# Arduino.net
KiCad netlist of a schematic drawn in Altium Designer
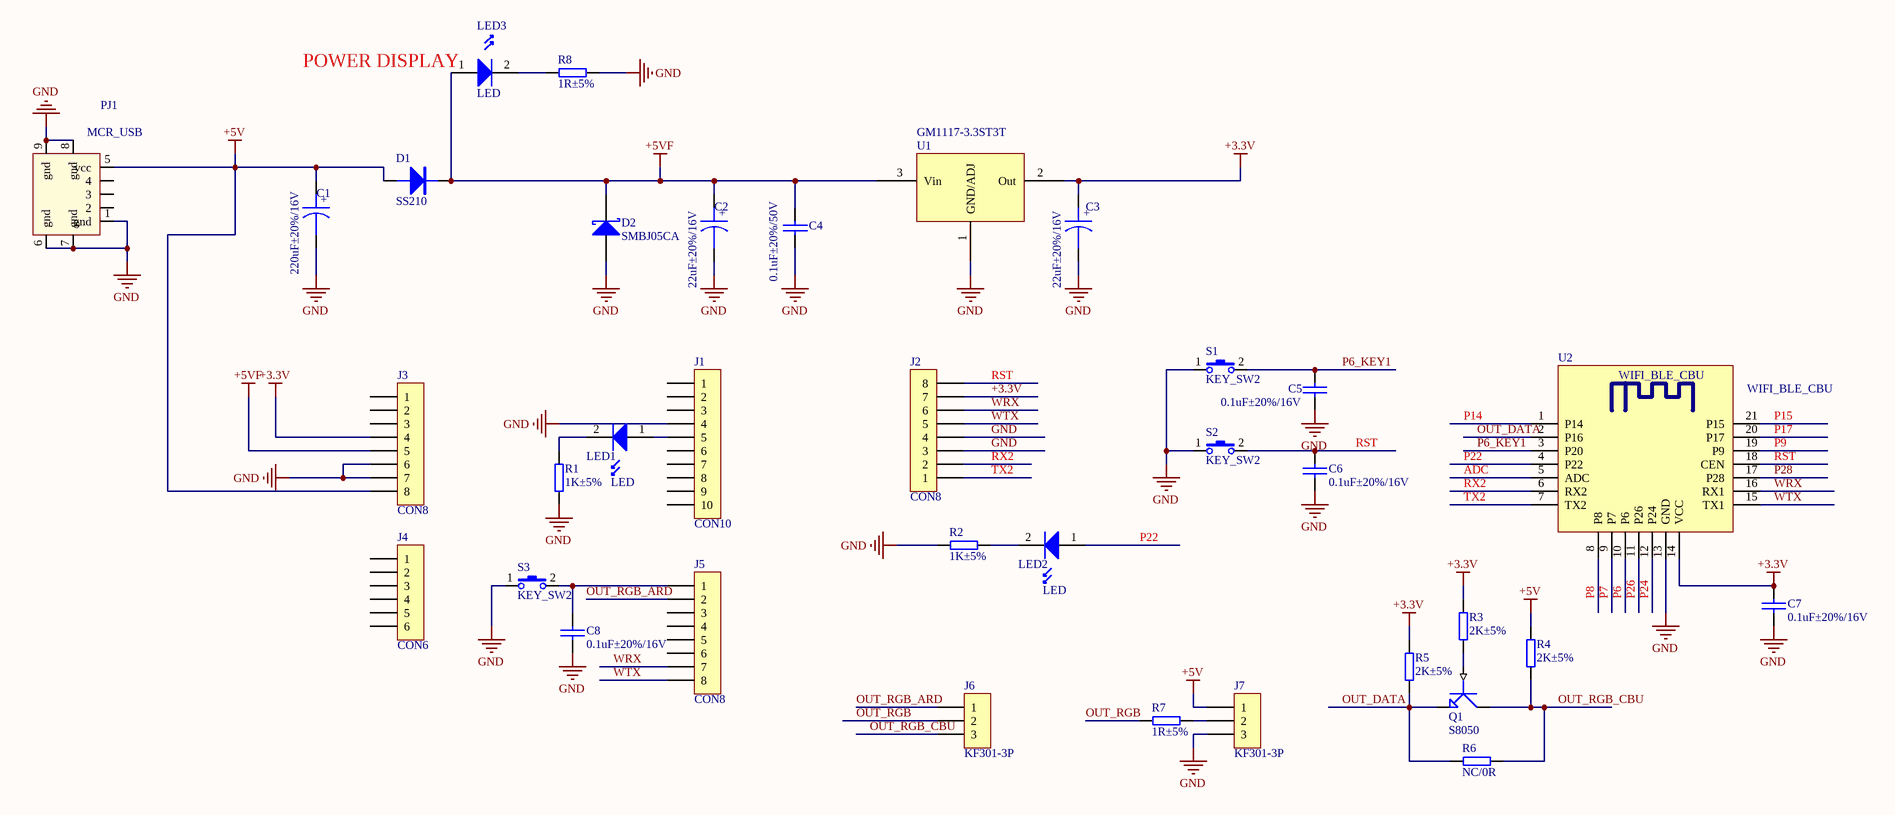
[diagram p0: Arduino幻彩灯带.SchDoc]

(export (version "E")
  (design (tool "Eeschema 10.0.6"))
  (components
    (comp (ref "C1")
      (value "220uF±20%/16V")
      (footprint "CD0.15")
      (description "Capacitor")
      (libsource (lib "*") (part "CAPACITOR POL"))
    )
    (comp (ref "C2")
      (value "22uF±20%/16V")
      (footprint "钽电容B3528")
      (description "Capacitor")
      (libsource (lib "*") (part "CAPACITOR POL"))
    )
    (comp (ref "C3")
      (value "22uF±20%/16V")
      (footprint "钽电容B3528")
      (description "Capacitor")
      (libsource (lib "*") (part "CAPACITOR POL"))
    )
    (comp (ref "C4")
      (value "0.1uF±20%/50V")
      (footprint "C0603")
      (description "Capacitor")
      (libsource (lib "昊华元件库sch") (part "CAP"))
    )
    (comp (ref "C5")
      (value "0.1uF±20%/16V")
      (footprint "C0603")
      (description "Capacitor")
      (libsource (lib "昊华元件库sch") (part "CAP"))
    )
    (comp (ref "C6")
      (value "0.1uF±20%/16V")
      (footprint "C0603")
      (description "Capacitor")
      (libsource (lib "昊华元件库sch") (part "CAP"))
    )
    (comp (ref "C7")
      (value "0.1uF±20%/16V")
      (footprint "C0603")
      (description "Capacitor")
      (libsource (lib "昊华元件库sch") (part "CAP"))
    )
    (comp (ref "C8")
      (value "0.1uF±20%/16V")
      (footprint "C0603")
      (description "Capacitor")
      (libsource (lib "昊华元件库sch") (part "CAP"))
    )
    (comp (ref "D1")
      (value "SS210")
      (footprint "SMA(DO-214AC)")
      (description "Diode")
      (libsource (lib "小马元件库sch") (part "Diode1"))
    )
    (comp (ref "D2")
      (value "SMBJ05CA")
      (footprint "SMB(DO-214AA)")
      (description "Schottky Diode")
      (fields (field (name "MFR") "Toshiba"))
      (libsource (lib "Miscellaneous Devices") (part "D Schottky"))
    )
    (comp (ref "J1")
      (value "CON10")
      (footprint "HDR1X10Z")
      (description "Connector")
      (libsource (lib "小马元件库sch") (part "CON10"))
    )
    (comp (ref "J2")
      (value "CON8")
      (footprint "HDR1X8Z")
      (description "Connector")
      (libsource (lib "小马元件库sch") (part "CON8"))
    )
    (comp (ref "J3")
      (value "CON8")
      (footprint "HDR1X8Z")
      (description "Connector")
      (libsource (lib "") (part "CON8_1"))
    )
    (comp (ref "J4")
      (value "CON6")
      (footprint "HDR1X6Z")
      (description "Connector")
      (libsource (lib "小马元件库sch") (part "CON6"))
    )
    (comp (ref "J5")
      (value "CON8")
      (footprint "HDR1X8Z")
      (description "Connector")
      (libsource (lib "") (part "CON8_1"))
    )
    (comp (ref "J6")
      (value "KF301-3P")
      (footprint "SIP3 - 2.54")
      (description "Connector")
      (libsource (lib "小马元件库sch") (part "CON3"))
    )
    (comp (ref "J7")
      (value "KF301-3P")
      (footprint "SIP3 - 2.54")
      (description "Connector")
      (libsource (lib "小马元件库sch") (part "CON3"))
    )
    (comp (ref "LED1")
      (value "LED")
      (footprint "LED0805_1")
      (fields (field (name "PUBLISHER") "*"))
      (libsource (lib "小马元件库sch") (part "LED"))
    )
    (comp (ref "LED2")
      (value "LED")
      (footprint "LED0805_1")
      (fields (field (name "PUBLISHER") "*"))
      (libsource (lib "小马元件库sch") (part "LED"))
    )
    (comp (ref "LED3")
      (value "LED")
      (footprint "LED0805_1")
      (fields (field (name "PUBLISHER") "*"))
      (libsource (lib "小马元件库sch") (part "LED"))
    )
    (comp (ref "PJ1")
      (value "MCR_USB")
      (footprint "MICRO_USB-NEW-16.12.12")
      (fields (field (name "PUBLISHER") "*"))
      (libsource (lib "昊华元件库sch") (part "MCR_USB"))
    )
    (comp (ref "Q1")
      (value "S8050")
      (footprint "SOT-23-NPN")
      (description "NPN Transistor")
      (libsource (lib "小马元件库sch") (part "NPN"))
    )
    (comp (ref "R1") (value "1K±5%") (footprint "R0603") (libsource (lib "昊华元件库sch") (part "RES5")))
    (comp (ref "R2") (value "1K±5%") (footprint "R0603") (libsource (lib "昊华元件库sch") (part "RES5")))
    (comp (ref "R3") (value "2K±5%") (footprint "R0603") (libsource (lib "昊华元件库sch") (part "RES5")))
    (comp (ref "R4") (value "2K±5%") (footprint "R0603") (libsource (lib "昊华元件库sch") (part "RES5")))
    (comp (ref "R5") (value "2K±5%") (footprint "R0603") (libsource (lib "昊华元件库sch") (part "RES5")))
    (comp (ref "R6") (value "NC/0R") (footprint "R0603") (libsource (lib "昊华元件库sch") (part "RES5")))
    (comp (ref "R7") (value "1R±5%") (footprint "R0603") (libsource (lib "昊华元件库sch") (part "RES5")))
    (comp (ref "R8") (value "1R±5%") (footprint "R0603") (libsource (lib "昊华元件库sch") (part "RES5")))
    (comp (ref "S1") (value "KEY_SW2") (footprint "KEY4-SMD") (libsource (lib "小马元件库sch") (part "KEY_SW2")))
    (comp (ref "S2") (value "KEY_SW2") (footprint "KEY4-SMD") (libsource (lib "小马元件库sch") (part "KEY_SW2")))
    (comp (ref "S3") (value "KEY_SW2") (footprint "KEY4-SMD") (libsource (lib "小马元件库sch") (part "KEY_SW2")))
    (comp (ref "U1") (value "GM1117-3.3ST3T") (footprint "SOT-223") (libsource (lib "mylib") (part "GM1117")))
    (comp (ref "U2")
      (value "WIFI_BLE_CBU")
      (footprint "WIFI_BLE_CBU")
      (description "Module")
      (libsource (lib "TYModeSchlib V03") (part "WIFI_BLE_CBU"))
    )
  )
  (nets
    (net (code "1") (name "+3.3V") (class "Default")
      (node (ref "C3") (pin "1") (pinfunction "1_1") (pintype "passive"))
      (node (ref "C7") (pin "2") (pinfunction "2_2") (pintype "passive"))
      (node (ref "J2") (pin "7") (pinfunction "7_7") (pintype "passive"))
      (node (ref "J3") (pin "4") (pinfunction "4_4") (pintype "passive"))
      (node (ref "R3") (pin "1") (pinfunction "1_1") (pintype "passive"))
      (node (ref "R5") (pin "1") (pinfunction "1_1") (pintype "passive"))
      (node (ref "U1") (pin "2") (pinfunction "Out_2") (pintype "passive"))
      (node (ref "U2") (pin "14") (pinfunction "VCC_14") (pintype "passive"))
    )
    (net (code "2") (name "+5V") (class "Default")
      (node (ref "C1") (pin "1") (pinfunction "1_1") (pintype "passive"))
      (node (ref "D1") (pin "1") (pinfunction "1_1") (pintype "passive"))
      (node (ref "J3") (pin "8") (pinfunction "8_8") (pintype "passive"))
      (node (ref "J7") (pin "1") (pinfunction "1_1") (pintype "passive"))
      (node (ref "PJ1") (pin "5") (pinfunction "vcc_5") (pintype "passive"))
      (node (ref "R4") (pin "1") (pinfunction "1_1") (pintype "passive"))
    )
    (net (code "3") (name "+5VF") (class "Default")
      (node (ref "C2") (pin "1") (pinfunction "1_1") (pintype "passive"))
      (node (ref "C4") (pin "1") (pinfunction "1_1") (pintype "passive"))
      (node (ref "D1") (pin "2") (pinfunction "2_2") (pintype "passive"))
      (node (ref "D2") (pin "2") (pinfunction "K_2") (pintype "passive"))
      (node (ref "J3") (pin "5") (pinfunction "5_5") (pintype "passive"))
      (node (ref "LED3") (pin "1") (pinfunction "1_1") (pintype "passive"))
      (node (ref "U1") (pin "3") (pinfunction "Vin_3") (pintype "passive"))
    )
    (net (code "4") (name "/ADC") (class "Default")
      (node (ref "U2") (pin "5") (pinfunction "ADC_5") (pintype "passive"))
    )
    (net (code "5") (name "/OUT_DATA") (class "Default")
      (node (ref "Q1") (pin "1") (pinfunction "E_1") (pintype "passive"))
      (node (ref "R5") (pin "2") (pinfunction "2_2") (pintype "passive"))
      (node (ref "R6") (pin "1") (pinfunction "1_1") (pintype "passive"))
      (node (ref "U2") (pin "2") (pinfunction "P16_2") (pintype "passive"))
    )
    (net (code "6") (name "/OUT_RGB") (class "Default")
      (node (ref "J6") (pin "2") (pinfunction "2_2") (pintype "passive"))
      (node (ref "R7") (pin "1") (pinfunction "1_1") (pintype "passive"))
    )
    (net (code "7") (name "/OUT_RGB_ARD") (class "Default")
      (node (ref "J5") (pin "2") (pinfunction "2_2") (pintype "passive"))
      (node (ref "J6") (pin "1") (pinfunction "1_1") (pintype "passive"))
    )
    (net (code "8") (name "/OUT_RGB_CBU") (class "Default")
      (node (ref "J6") (pin "3") (pinfunction "3_3") (pintype "passive"))
      (node (ref "Q1") (pin "3") (pinfunction "C_3") (pintype "passive"))
      (node (ref "R4") (pin "2") (pinfunction "2_2") (pintype "passive"))
      (node (ref "R6") (pin "2") (pinfunction "2_2") (pintype "passive"))
    )
    (net (code "9") (name "/P6") (class "Default")
      (node (ref "U2") (pin "10") (pinfunction "P6_10") (pintype "passive"))
    )
    (net (code "10") (name "/P6_KEY1") (class "Default")
      (node (ref "C5") (pin "2") (pinfunction "2_2") (pintype "passive"))
      (node (ref "S1") (pin "2") (pinfunction "2_2") (pintype "passive"))
      (node (ref "U2") (pin "3") (pinfunction "P20_3") (pintype "passive"))
    )
    (net (code "11") (name "/P7") (class "Default")
      (node (ref "U2") (pin "9") (pinfunction "P7_9") (pintype "passive"))
    )
    (net (code "12") (name "/P8") (class "Default")
      (node (ref "U2") (pin "8") (pinfunction "P8_8") (pintype "passive"))
    )
    (net (code "13") (name "/P9") (class "Default")
      (node (ref "U2") (pin "19") (pinfunction "P9_19") (pintype "passive"))
    )
    (net (code "14") (name "/P14") (class "Default")
      (node (ref "U2") (pin "1") (pinfunction "P14_1") (pintype "passive"))
    )
    (net (code "15") (name "/P15") (class "Default")
      (node (ref "U2") (pin "21") (pinfunction "P15_21") (pintype "passive"))
    )
    (net (code "16") (name "/P17") (class "Default")
      (node (ref "U2") (pin "20") (pinfunction "P17_20") (pintype "passive"))
    )
    (net (code "17") (name "/P22") (class "Default")
      (node (ref "LED2") (pin "1") (pinfunction "1_1") (pintype "passive"))
      (node (ref "U2") (pin "4") (pinfunction "P22_4") (pintype "passive"))
    )
    (net (code "18") (name "/P24") (class "Default")
      (node (ref "U2") (pin "12") (pinfunction "P24_12") (pintype "passive"))
    )
    (net (code "19") (name "/P26") (class "Default")
      (node (ref "U2") (pin "11") (pinfunction "P26_11") (pintype "passive"))
    )
    (net (code "20") (name "/P28") (class "Default")
      (node (ref "U2") (pin "17") (pinfunction "P28_17") (pintype "passive"))
    )
    (net (code "21") (name "/RST") (class "Default")
      (node (ref "C6") (pin "1") (pinfunction "1_1") (pintype "passive"))
      (node (ref "J2") (pin "8") (pinfunction "8_8") (pintype "passive"))
      (node (ref "S2") (pin "2") (pinfunction "2_2") (pintype "passive"))
      (node (ref "U2") (pin "18") (pinfunction "CEN_18") (pintype "passive"))
    )
    (net (code "22") (name "/RX2") (class "Default")
      (node (ref "J2") (pin "2") (pinfunction "2_2") (pintype "passive"))
      (node (ref "U2") (pin "6") (pinfunction "RX2_6") (pintype "passive"))
    )
    (net (code "23") (name "/TX2") (class "Default")
      (node (ref "J2") (pin "1") (pinfunction "1_1") (pintype "passive"))
      (node (ref "U2") (pin "7") (pinfunction "TX2_7") (pintype "passive"))
    )
    (net (code "24") (name "/WRX") (class "Default")
      (node (ref "J2") (pin "6") (pinfunction "6_6") (pintype "passive"))
      (node (ref "J5") (pin "7") (pinfunction "7_7") (pintype "passive"))
      (node (ref "U2") (pin "16") (pinfunction "RX1_16") (pintype "passive"))
    )
    (net (code "25") (name "/WTX") (class "Default")
      (node (ref "J2") (pin "5") (pinfunction "5_5") (pintype "passive"))
      (node (ref "J5") (pin "8") (pinfunction "8_8") (pintype "passive"))
      (node (ref "U2") (pin "15") (pinfunction "TX1_15") (pintype "passive"))
    )
    (net (code "26") (name "GND") (class "Default")
      (node (ref "C1") (pin "2") (pinfunction "2_2") (pintype "passive"))
      (node (ref "C2") (pin "2") (pinfunction "2_2") (pintype "passive"))
      (node (ref "C3") (pin "2") (pinfunction "2_2") (pintype "passive"))
      (node (ref "C4") (pin "2") (pinfunction "2_2") (pintype "passive"))
      (node (ref "C5") (pin "1") (pinfunction "1_1") (pintype "passive"))
      (node (ref "C6") (pin "2") (pinfunction "2_2") (pintype "passive"))
      (node (ref "C7") (pin "1") (pinfunction "1_1") (pintype "passive"))
      (node (ref "C8") (pin "1") (pinfunction "1_1") (pintype "passive"))
      (node (ref "D2") (pin "1") (pinfunction "A_1") (pintype "passive"))
      (node (ref "J1") (pin "4") (pinfunction "4_4") (pintype "passive"))
      (node (ref "J2") (pin "3") (pinfunction "3_3") (pintype "passive"))
      (node (ref "J2") (pin "4") (pinfunction "4_4") (pintype "passive"))
      (node (ref "J3") (pin "6") (pinfunction "6_6") (pintype "passive"))
      (node (ref "J3") (pin "7") (pinfunction "7_7") (pintype "passive"))
      (node (ref "J7") (pin "3") (pinfunction "3_3") (pintype "passive"))
      (node (ref "PJ1") (pin "1") (pinfunction "gnd_1") (pintype "passive"))
      (node (ref "PJ1") (pin "6") (pinfunction "gnd_6") (pintype "passive"))
      (node (ref "PJ1") (pin "7") (pinfunction "gnd_7") (pintype "passive"))
      (node (ref "PJ1") (pin "8") (pinfunction "gnd_8") (pintype "passive"))
      (node (ref "PJ1") (pin "9") (pinfunction "gnd_9") (pintype "passive"))
      (node (ref "R1") (pin "1") (pinfunction "1_1") (pintype "passive"))
      (node (ref "R2") (pin "2") (pinfunction "2_2") (pintype "passive"))
      (node (ref "R8") (pin "2") (pinfunction "2_2") (pintype "passive"))
      (node (ref "S1") (pin "1") (pinfunction "1_1") (pintype "passive"))
      (node (ref "S2") (pin "1") (pinfunction "1_1") (pintype "passive"))
      (node (ref "S3") (pin "1") (pinfunction "1_1") (pintype "passive"))
      (node (ref "U1") (pin "1") (pinfunction "GND/ADJ_1") (pintype "passive"))
      (node (ref "U2") (pin "13") (pinfunction "GND_13") (pintype "passive"))
    )
    (net (code "27") (name "Net-(C8-Pad2)") (class "Default")
      (node (ref "C8") (pin "2") (pinfunction "2_2") (pintype "passive"))
      (node (ref "J5") (pin "1") (pinfunction "1_1") (pintype "passive"))
      (node (ref "S3") (pin "2") (pinfunction "2_2") (pintype "passive"))
    )
    (net (code "28") (name "Net-(J1-Pad5)") (class "Default")
      (node (ref "J1") (pin "5") (pinfunction "5_5") (pintype "passive"))
      (node (ref "LED1") (pin "1") (pinfunction "1_1") (pintype "passive"))
    )
    (net (code "29") (name "Net-(J7-Pad2)") (class "Default")
      (node (ref "J7") (pin "2") (pinfunction "2_2") (pintype "passive"))
      (node (ref "R7") (pin "2") (pinfunction "2_2") (pintype "passive"))
    )
    (net (code "30") (name "Net-(LED1-Pad2)") (class "Default")
      (node (ref "LED1") (pin "2") (pinfunction "2_2") (pintype "passive"))
      (node (ref "R1") (pin "2") (pinfunction "2_2") (pintype "passive"))
    )
    (net (code "31") (name "Net-(LED2-Pad2)") (class "Default")
      (node (ref "LED2") (pin "2") (pinfunction "2_2") (pintype "passive"))
      (node (ref "R2") (pin "1") (pinfunction "1_1") (pintype "passive"))
    )
    (net (code "32") (name "Net-(LED3-Pad2)") (class "Default")
      (node (ref "LED3") (pin "2") (pinfunction "2_2") (pintype "passive"))
      (node (ref "R8") (pin "1") (pinfunction "1_1") (pintype "passive"))
    )
    (net (code "33") (name "Net-(Q1-B)") (class "Default")
      (node (ref "Q1") (pin "2") (pinfunction "B_2") (pintype "input"))
      (node (ref "R3") (pin "2") (pinfunction "2_2") (pintype "passive"))
    )
    (net (code "34") (name "unconnected-(J1-Pad1)") (class "Default")
      (node (ref "J1") (pin "1") (pinfunction "1_1") (pintype "passive"))
    )
    (net (code "35") (name "unconnected-(J1-Pad2)") (class "Default")
      (node (ref "J1") (pin "2") (pinfunction "2_2") (pintype "passive"))
    )
    (net (code "36") (name "unconnected-(J1-Pad3)") (class "Default")
      (node (ref "J1") (pin "3") (pinfunction "3_3") (pintype "passive"))
    )
    (net (code "37") (name "unconnected-(J1-Pad6)") (class "Default")
      (node (ref "J1") (pin "6") (pinfunction "6_6") (pintype "passive"))
    )
    (net (code "38") (name "unconnected-(J1-Pad7)") (class "Default")
      (node (ref "J1") (pin "7") (pinfunction "7_7") (pintype "passive"))
    )
    (net (code "39") (name "unconnected-(J1-Pad8)") (class "Default")
      (node (ref "J1") (pin "8") (pinfunction "8_8") (pintype "passive"))
    )
    (net (code "40") (name "unconnected-(J1-Pad9)") (class "Default")
      (node (ref "J1") (pin "9") (pinfunction "9_9") (pintype "passive"))
    )
    (net (code "41") (name "unconnected-(J1-Pad10)") (class "Default")
      (node (ref "J1") (pin "10") (pinfunction "10_10") (pintype "passive"))
    )
    (net (code "42") (name "unconnected-(J3-Pad1)") (class "Default")
      (node (ref "J3") (pin "1") (pinfunction "1_1") (pintype "passive"))
    )
    (net (code "43") (name "unconnected-(J3-Pad2)") (class "Default")
      (node (ref "J3") (pin "2") (pinfunction "2_2") (pintype "passive"))
    )
    (net (code "44") (name "unconnected-(J3-Pad3)") (class "Default")
      (node (ref "J3") (pin "3") (pinfunction "3_3") (pintype "passive"))
    )
    (net (code "45") (name "unconnected-(J4-Pad1)") (class "Default")
      (node (ref "J4") (pin "1") (pinfunction "1_1") (pintype "passive"))
    )
    (net (code "46") (name "unconnected-(J4-Pad2)") (class "Default")
      (node (ref "J4") (pin "2") (pinfunction "2_2") (pintype "passive"))
    )
    (net (code "47") (name "unconnected-(J4-Pad3)") (class "Default")
      (node (ref "J4") (pin "3") (pinfunction "3_3") (pintype "passive"))
    )
    (net (code "48") (name "unconnected-(J4-Pad4)") (class "Default")
      (node (ref "J4") (pin "4") (pinfunction "4_4") (pintype "passive"))
    )
    (net (code "49") (name "unconnected-(J4-Pad5)") (class "Default")
      (node (ref "J4") (pin "5") (pinfunction "5_5") (pintype "passive"))
    )
    (net (code "50") (name "unconnected-(J4-Pad6)") (class "Default")
      (node (ref "J4") (pin "6") (pinfunction "6_6") (pintype "passive"))
    )
    (net (code "51") (name "unconnected-(J5-Pad3)") (class "Default")
      (node (ref "J5") (pin "3") (pinfunction "3_3") (pintype "passive"))
    )
    (net (code "52") (name "unconnected-(J5-Pad4)") (class "Default")
      (node (ref "J5") (pin "4") (pinfunction "4_4") (pintype "passive"))
    )
    (net (code "53") (name "unconnected-(J5-Pad5)") (class "Default")
      (node (ref "J5") (pin "5") (pinfunction "5_5") (pintype "passive"))
    )
    (net (code "54") (name "unconnected-(J5-Pad6)") (class "Default")
      (node (ref "J5") (pin "6") (pinfunction "6_6") (pintype "passive"))
    )
    (net (code "55") (name "unconnected-(PJ1-Pad2)") (class "Default")
      (node (ref "PJ1") (pin "2") (pinfunction "2_2") (pintype "passive"))
    )
    (net (code "56") (name "unconnected-(PJ1-Pad3)") (class "Default")
      (node (ref "PJ1") (pin "3") (pinfunction "3_3") (pintype "passive"))
    )
    (net (code "57") (name "unconnected-(PJ1-Pad4)") (class "Default")
      (node (ref "PJ1") (pin "4") (pinfunction "4_4") (pintype "passive"))
    )
  )
)
